# crazyflie_radio_2_0.net
KiCad netlist of a schematic drawn in EAGLE
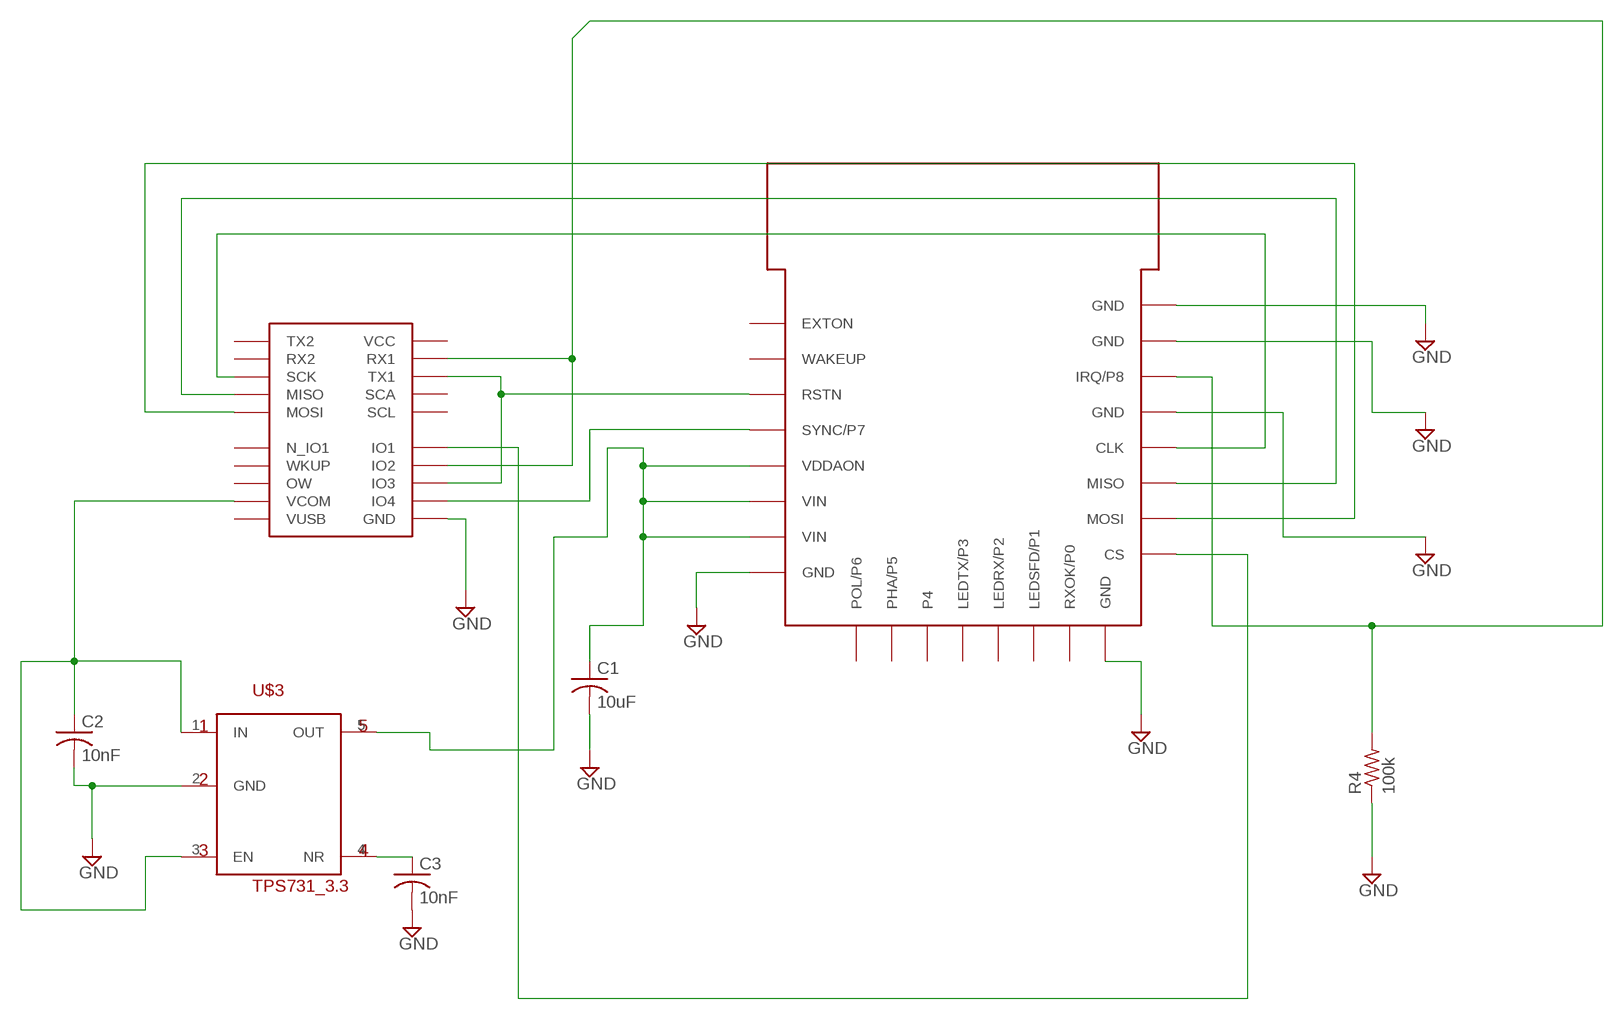
[diagram p0: schematic, sheet 1]

(export (version "E")
  (design (tool "Eeschema 10.0.6"))
  (components
    (comp (ref "C1")
      (value "10uF")
      (footprint "eagle-import:C0402")
      (libsource (lib "eagle-import") (part "C-USC0402"))
    )
    (comp (ref "C2")
      (value "10nF")
      (footprint "eagle-import:C0402")
      (libsource (lib "eagle-import") (part "C-USC0402"))
    )
    (comp (ref "C3")
      (value "10nF")
      (footprint "eagle-import:C0402")
      (libsource (lib "eagle-import") (part "C-USC0402"))
    )
    (comp (ref "R4")
      (value "100k")
      (footprint "eagle-import:R0402")
      (libsource (lib "eagle-import") (part "R-US_R0402"))
    )
    (comp (ref "U$1")
      (value "DWM100")
      (footprint "eagle-import:DWMPAC")
      (libsource (lib "eagle-import") (part "DWM100"))
    )
    (comp (ref "U$2")
      (value "CFHEAD")
      (footprint "eagle-import:CFHEADPAC")
      (libsource (lib "eagle-import") (part "CFHEAD"))
    )
    (comp (ref "U$3")
      (value "TPS731_3.3")
      (footprint "eagle-import:SOT-23-5")
      (libsource (lib "eagle-import") (part "TPS731_3.3"))
    )
  )
  (nets
    (net (code "1") (name "GND") (class "Default")
      (node (ref "C1") (pin "2") (pinfunction "2_2") (pintype "passive"))
      (node (ref "C2") (pin "2") (pinfunction "2_2") (pintype "passive"))
      (node (ref "C3") (pin "2") (pinfunction "2_2") (pintype "passive"))
      (node (ref "R4") (pin "1") (pinfunction "1_1") (pintype "passive"))
      (node (ref "U$1") (pin "GND@1") (pinfunction "GND_GND@1") (pintype "bidirectional"))
      (node (ref "U$1") (pin "GND@2") (pinfunction "GND_GND@2") (pintype "bidirectional"))
      (node (ref "U$1") (pin "GND@3") (pinfunction "GND_GND@3") (pintype "bidirectional"))
      (node (ref "U$1") (pin "GND@4") (pinfunction "GND_GND@4") (pintype "bidirectional"))
      (node (ref "U$1") (pin "GND@5") (pinfunction "GND_GND@5") (pintype "bidirectional"))
      (node (ref "U$2") (pin "GND") (pinfunction "GND_GND") (pintype "bidirectional"))
      (node (ref "U$3") (pin "2") (pinfunction "GND_2") (pintype "bidirectional"))
    )
    (net (code "2") (name "Net-(R4-Pad2)") (class "Default")
      (node (ref "R4") (pin "2") (pinfunction "2_2") (pintype "passive"))
      (node (ref "U$1") (pin "IRQ/P8") (pinfunction "IRQ/P8_IRQ/P8") (pintype "bidirectional"))
      (node (ref "U$2") (pin "IO2") (pinfunction "IO2_IO2") (pintype "bidirectional"))
      (node (ref "U$2") (pin "RX1") (pinfunction "RX1_RX1") (pintype "bidirectional"))
    )
    (net (code "3") (name "Net-(U$1-PadCLK)") (class "Default")
      (node (ref "U$1") (pin "CLK") (pinfunction "CLK_CLK") (pintype "bidirectional"))
      (node (ref "U$2") (pin "SCK") (pinfunction "SCK_SCK") (pintype "bidirectional"))
    )
    (net (code "4") (name "Net-(U$1-PadCS)") (class "Default")
      (node (ref "U$1") (pin "CS") (pinfunction "CS_CS") (pintype "bidirectional"))
      (node (ref "U$2") (pin "IO1") (pinfunction "IO1_IO1") (pintype "bidirectional"))
    )
    (net (code "5") (name "Net-(U$1-PadMISO)") (class "Default")
      (node (ref "U$1") (pin "MISO") (pinfunction "MISO_MISO") (pintype "bidirectional"))
      (node (ref "U$2") (pin "MISO") (pinfunction "MISO_MISO") (pintype "bidirectional"))
    )
    (net (code "6") (name "Net-(U$1-PadMOSI)") (class "Default")
      (node (ref "U$1") (pin "MOSI") (pinfunction "MOSI_MOSI") (pintype "bidirectional"))
      (node (ref "U$2") (pin "MOSI") (pinfunction "MOSI_MOSI") (pintype "bidirectional"))
    )
    (net (code "7") (name "Net-(U$1-PadRSTN)") (class "Default")
      (node (ref "U$1") (pin "RSTN") (pinfunction "RSTN_RSTN") (pintype "bidirectional"))
      (node (ref "U$2") (pin "IO3") (pinfunction "IO3_IO3") (pintype "bidirectional"))
      (node (ref "U$2") (pin "TX1") (pinfunction "TX1_TX1") (pintype "bidirectional"))
    )
    (net (code "8") (name "Net-(U$1-PadSYNC{slash}P7)") (class "Default")
      (node (ref "U$1") (pin "SYNC/P7") (pinfunction "SYNC/P7_SYNC/P7") (pintype "bidirectional"))
      (node (ref "U$2") (pin "IO4") (pinfunction "IO4_IO4") (pintype "bidirectional"))
    )
    (net (code "9") (name "Net-(U$3-EN)") (class "Default")
      (node (ref "C2") (pin "1") (pinfunction "1_1") (pintype "passive"))
      (node (ref "U$2") (pin "VCOM") (pinfunction "VCOM_VCOM") (pintype "bidirectional"))
      (node (ref "U$3") (pin "1") (pinfunction "IN_1") (pintype "bidirectional"))
      (node (ref "U$3") (pin "3") (pinfunction "EN_3") (pintype "bidirectional"))
    )
    (net (code "10") (name "Net-(U$3-NR)") (class "Default")
      (node (ref "C3") (pin "1") (pinfunction "1_1") (pintype "passive"))
      (node (ref "U$3") (pin "4") (pinfunction "NR_4") (pintype "bidirectional"))
    )
    (net (code "11") (name "Net-(U$3-OUT)") (class "Default")
      (node (ref "C1") (pin "1") (pinfunction "1_1") (pintype "passive"))
      (node (ref "U$1") (pin "VDDAON") (pinfunction "VDDAON_VDDAON") (pintype "bidirectional"))
      (node (ref "U$1") (pin "VIN@1") (pinfunction "VIN_VIN@1") (pintype "bidirectional"))
      (node (ref "U$1") (pin "VIN@2") (pinfunction "VIN_VIN@2") (pintype "bidirectional"))
      (node (ref "U$3") (pin "5") (pinfunction "OUT_5") (pintype "bidirectional"))
    )
    (net (code "12") (name "unconnected-(U$1-PadEXTON)") (class "Default")
      (node (ref "U$1") (pin "EXTON") (pinfunction "EXTON_EXTON") (pintype "bidirectional"))
    )
    (net (code "13") (name "unconnected-(U$1-PadLEDRX{slash}P2)") (class "Default")
      (node (ref "U$1") (pin "LEDRX/P2") (pinfunction "LEDRX/P2_LEDRX/P2") (pintype "bidirectional"))
    )
    (net (code "14") (name "unconnected-(U$1-PadLEDSFD{slash}P1)") (class "Default")
      (node (ref "U$1") (pin "LEDSFD/P1") (pinfunction "LEDSFD/P1_LEDSFD/P1") (pintype "bidirectional"))
    )
    (net (code "15") (name "unconnected-(U$1-PadLEDTX{slash}P3)") (class "Default")
      (node (ref "U$1") (pin "LEDTX/P3") (pinfunction "LEDTX/P3_LEDTX/P3") (pintype "bidirectional"))
    )
    (net (code "16") (name "unconnected-(U$1-PadP4)") (class "Default")
      (node (ref "U$1") (pin "P4") (pinfunction "P4_P4") (pintype "bidirectional"))
    )
    (net (code "17") (name "unconnected-(U$1-PadPHA{slash}P5)") (class "Default")
      (node (ref "U$1") (pin "PHA/P5") (pinfunction "PHA/P5_PHA/P5") (pintype "bidirectional"))
    )
    (net (code "18") (name "unconnected-(U$1-PadPOL{slash}P6)") (class "Default")
      (node (ref "U$1") (pin "POL/P6") (pinfunction "POL/P6_POL/P6") (pintype "bidirectional"))
    )
    (net (code "19") (name "unconnected-(U$1-PadRXOK{slash}P0)") (class "Default")
      (node (ref "U$1") (pin "RXOK/P0") (pinfunction "RXOK/P0_RXOK/P0") (pintype "bidirectional"))
    )
    (net (code "20") (name "unconnected-(U$1-PadWAKEUP)") (class "Default")
      (node (ref "U$1") (pin "WAKEUP") (pinfunction "WAKEUP_WAKEUP") (pintype "bidirectional"))
    )
    (net (code "21") (name "unconnected-(U$2-PadN_IO1)") (class "Default")
      (node (ref "U$2") (pin "N_IO1") (pinfunction "N_IO1_N_IO1") (pintype "bidirectional"))
    )
    (net (code "22") (name "unconnected-(U$2-PadOW)") (class "Default")
      (node (ref "U$2") (pin "OW") (pinfunction "OW_OW") (pintype "bidirectional"))
    )
    (net (code "23") (name "unconnected-(U$2-PadRX2)") (class "Default")
      (node (ref "U$2") (pin "RX2") (pinfunction "RX2_RX2") (pintype "bidirectional"))
    )
    (net (code "24") (name "unconnected-(U$2-PadSCA)") (class "Default")
      (node (ref "U$2") (pin "SCA") (pinfunction "SCA_SCA") (pintype "bidirectional"))
    )
    (net (code "25") (name "unconnected-(U$2-PadSCL)") (class "Default")
      (node (ref "U$2") (pin "SCL") (pinfunction "SCL_SCL") (pintype "bidirectional"))
    )
    (net (code "26") (name "unconnected-(U$2-PadTX2)") (class "Default")
      (node (ref "U$2") (pin "TX2") (pinfunction "TX2_TX2") (pintype "bidirectional"))
    )
    (net (code "27") (name "unconnected-(U$2-PadVCC)") (class "Default")
      (node (ref "U$2") (pin "VCC") (pinfunction "VCC_VCC") (pintype "bidirectional"))
    )
    (net (code "28") (name "unconnected-(U$2-PadVUSB)") (class "Default")
      (node (ref "U$2") (pin "VUSB") (pinfunction "VUSB_VUSB") (pintype "bidirectional"))
    )
    (net (code "29") (name "unconnected-(U$2-PadWKUP)") (class "Default")
      (node (ref "U$2") (pin "WKUP") (pinfunction "WKUP_WKUP") (pintype "bidirectional"))
    )
  )
)
